# Cat_feeder.net
KiCad netlist of a schematic drawn in Altium Designer
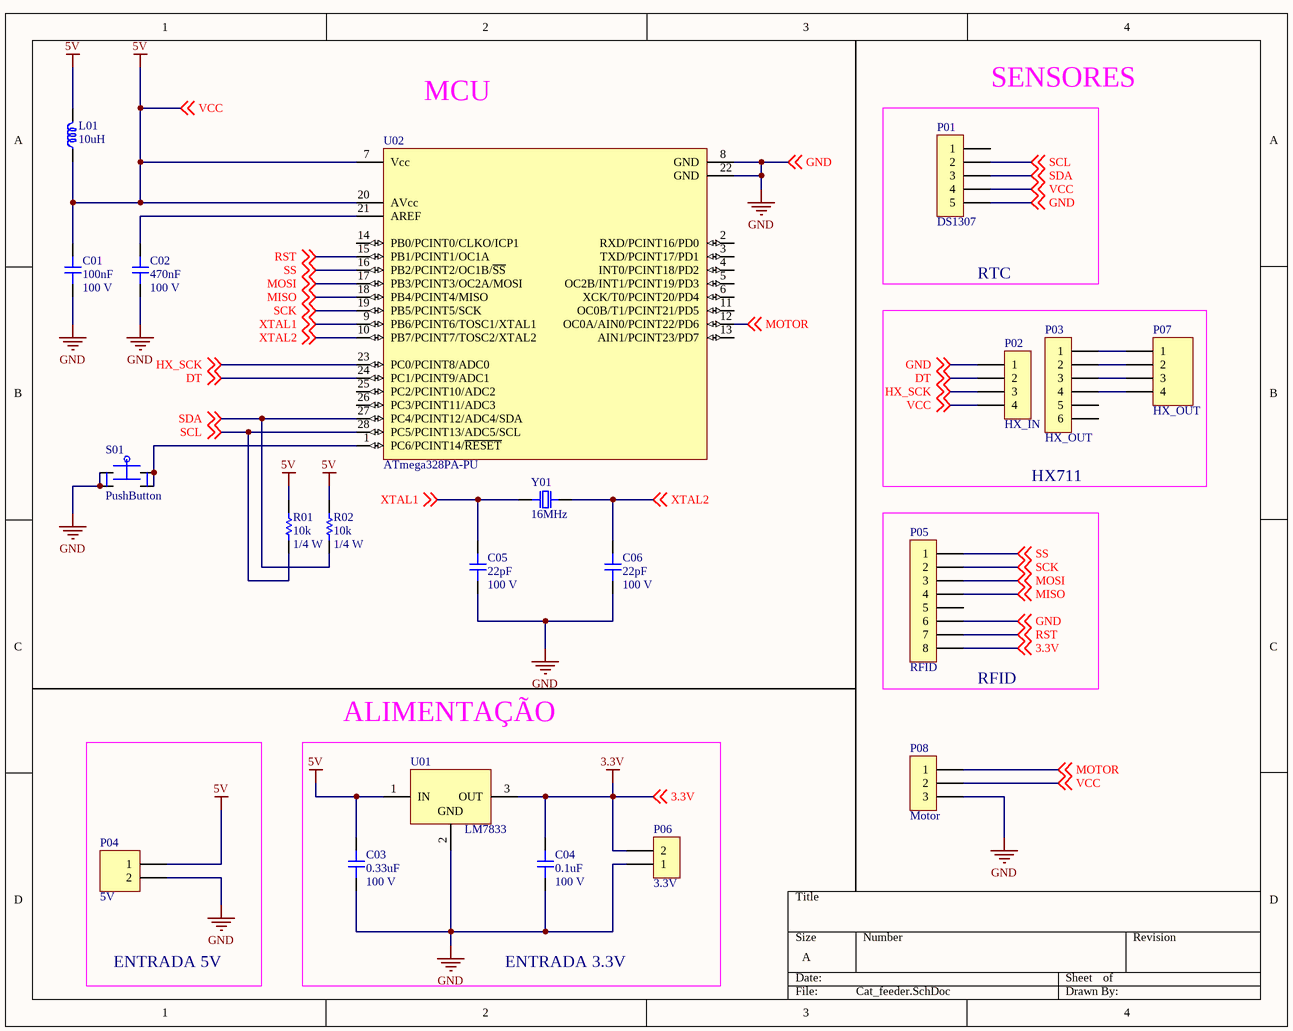
[diagram p0: Cat_feeder.SchDoc]

(export (version "E")
  (design (tool "Eeschema 10.0.6"))
  (components
    (comp (ref "C01")
      (value "100nF")
      (footprint "C100-200-100")
      (description "Capacitor")
      (fields (field (name "VOLTAGE") "100 V") (field (name "PUBLISHER") "Altium Limited"))
      (libsource (lib "GPDSE") (part "Capacitor"))
    )
    (comp (ref "C02")
      (value "470nF")
      (footprint "C100-200-100")
      (description "Capacitor")
      (fields (field (name "VOLTAGE") "100 V") (field (name "PUBLISHER") "Altium Limited"))
      (libsource (lib "GPDSE") (part "Capacitor"))
    )
    (comp (ref "C03")
      (value "0.33uF")
      (footprint "C200-350-150")
      (description "Capacitor")
      (fields (field (name "VOLTAGE") "100 V") (field (name "PUBLISHER") "Altium Limited"))
      (libsource (lib "GPDSE") (part "Capacitor"))
    )
    (comp (ref "C04")
      (value "0.1uF")
      (footprint "C200-350-150")
      (description "Capacitor")
      (fields (field (name "VOLTAGE") "100 V") (field (name "PUBLISHER") "Altium Limited"))
      (libsource (lib "GPDSE") (part "Capacitor"))
    )
    (comp (ref "C05")
      (value "22pF")
      (footprint "C100-200-100")
      (description "Capacitor")
      (fields (field (name "VOLTAGE") "100 V") (field (name "PUBLISHER") "Altium Limited"))
      (libsource (lib "GPDSE") (part "Capacitor"))
    )
    (comp (ref "C06")
      (value "22pF")
      (footprint "C100-200-100")
      (description "Capacitor")
      (fields (field (name "VOLTAGE") "100 V") (field (name "PUBLISHER") "Altium Limited"))
      (libsource (lib "GPDSE") (part "Capacitor"))
    )
    (comp (ref "L01")
      (value "10uH")
      (footprint "L400-2.0mm")
      (description "Inductor")
      (libsource (lib "GPDSE") (part "Inductor"))
    )
    (comp (ref "P01")
      (value "DS1307")
      (footprint "HDR-M-1x5-2.54mm-180-9.2mm")
      (description "Header, 1 Line, 5 Columns, 5 Pins")
      (fields (field (name "PUBLISHER") "Altium Limited"))
      (libsource (lib "GPDSE") (part "Header_1x5"))
    )
    (comp (ref "P02")
      (value "HX_IN")
      (footprint "HDR-M-1x4-2.54mm-180-21.1mm")
      (description "Header, 1 Line, 4 Columns, 4 Pins")
      (fields (field (name "PUBLISHER") "Altium Limited"))
      (libsource (lib "GPDSE") (part "Header_1x4"))
    )
    (comp (ref "P03")
      (value "HX_OUT")
      (footprint "HDR-M-1x6-2.54mm-180-9.2mm")
      (description "Header, 1 Line, 6 Columns, 6 Pins")
      (fields (field (name "PUBLISHER") "Altium Limited"))
      (libsource (lib "GPDSE") (part "Header_1x6"))
    )
    (comp (ref "P04")
      (value "5V")
      (footprint "KRE_2")
      (description "Terminal Block 1x2")
      (libsource (lib "GPDSE") (part "KRE_2"))
    )
    (comp (ref "P05")
      (value "RFID")
      (footprint "HDR-M-1x8-2.54mm-180-9.2mm")
      (description "Header, 1 Line, 8 Columns, 8 Pins")
      (fields (field (name "PUBLISHER") "Altium Limited"))
      (libsource (lib "GPDSE") (part "Header_1x8"))
    )
    (comp (ref "P06")
      (value "3.3V")
      (footprint "HDR-M-1x2-2.54mm-180-9.2mm")
      (description "Header, 1 Line, 2 Columns, 2 Pins")
      (fields (field (name "PUBLISHER") "Altium Limited"))
      (libsource (lib "GPDSE") (part "Header_1x2"))
    )
    (comp (ref "P07")
      (value "HX_OUT")
      (footprint "KRE_4")
      (description "Terminal Block 1x4")
      (libsource (lib "GPDSE") (part "KRE_4"))
    )
    (comp (ref "P08")
      (value "Motor")
      (footprint "HDR-M-1x3-2.54mm-180-9.2mm")
      (description "Header, 1 Line, 3 Columns, 3 Pins")
      (fields (field (name "PUBLISHER") "Altium Limited"))
      (libsource (lib "GPDSE") (part "Header_1x3"))
    )
    (comp (ref "R01")
      (value "10k")
      (footprint "R400-2.0mm")
      (description "Resistor")
      (fields
        (field (name "TOLERANCE") "5%")
        (field (name "POWER") "1/4 W")
        (field (name "PUBLISHER") "Altium Limited")
      )
      (libsource (lib "GPDSE") (part "Resistor"))
    )
    (comp (ref "R02")
      (value "10k")
      (footprint "R400-2.0mm")
      (description "Resistor")
      (fields
        (field (name "TOLERANCE") "5%")
        (field (name "POWER") "1/4 W")
        (field (name "PUBLISHER") "Altium Limited")
      )
      (libsource (lib "GPDSE") (part "Resistor"))
    )
    (comp (ref "S01")
      (value "PushButton")
      (footprint "DTS-6.0mm-6.0mm-THT")
      (description "Tactile Switch SPST 4 pins")
      (libsource (lib "GPDSE") (part "PushButton_4"))
    )
    (comp (ref "U01")
      (value "LM7833")
      (footprint "TO-220/123")
      (description "3-Terminal 1 A Positive 5 V Voltage Regulator")
      (libsource (lib "GPDSE") (part "LM7805CT"))
    )
    (comp (ref "U02")
      (value "ATmega328PA-PU")
      (footprint "DIP28-300(100)")
      (description "8-bit AVR Microcontroller with 32 KB In-System Programmable Flash")
      (libsource (lib "GPDSE") (part "ATmega328PA-PU"))
    )
    (comp (ref "Y01")
      (value "16MHz")
      (footprint "HC49-US-THT")
      (description "Crystal")
      (libsource (lib "GPDSE") (part "Crystal"))
    )
  )
  (nets
    (net (code "1") (name "3.3V") (class "Default")
      (node (ref "C04") (pin "2") (pinfunction "2_2") (pintype "passive"))
      (node (ref "P05") (pin "8") (pinfunction "8_8") (pintype "passive"))
      (node (ref "P06") (pin "2") (pinfunction "2_2") (pintype "passive"))
      (node (ref "U01") (pin "3") (pinfunction "OUT_3") (pintype "passive"))
    )
    (net (code "2") (name "5V") (class "Default")
      (node (ref "C01") (pin "2") (pinfunction "2_2") (pintype "passive"))
      (node (ref "C03") (pin "2") (pinfunction "2_2") (pintype "passive"))
      (node (ref "L01") (pin "1") (pinfunction "1_1") (pintype "passive"))
      (node (ref "L01") (pin "2") (pinfunction "2_2") (pintype "passive"))
      (node (ref "P01") (pin "4") (pinfunction "4_4") (pintype "passive"))
      (node (ref "P02") (pin "4") (pinfunction "4_4") (pintype "passive"))
      (node (ref "P04") (pin "1") (pinfunction "1_1") (pintype "passive"))
      (node (ref "P08") (pin "2") (pinfunction "2_2") (pintype "passive"))
      (node (ref "R01") (pin "2") (pinfunction "2_2") (pintype "passive"))
      (node (ref "R02") (pin "2") (pinfunction "2_2") (pintype "passive"))
      (node (ref "U01") (pin "1") (pinfunction "IN_1") (pintype "passive"))
      (node (ref "U02") (pin "20") (pinfunction "AVcc_20") (pintype "passive"))
      (node (ref "U02") (pin "7") (pinfunction "Vcc_7") (pintype "passive"))
    )
    (net (code "3") (name "DT") (class "Default")
      (node (ref "P02") (pin "2") (pinfunction "2_2") (pintype "passive"))
      (node (ref "U02") (pin "24") (pinfunction "PC1/PCINT9/ADC1_24") (pintype "bidirectional"))
    )
    (net (code "4") (name "GND") (class "Default")
      (node (ref "C01") (pin "1") (pinfunction "1_1") (pintype "passive"))
      (node (ref "C02") (pin "1") (pinfunction "1_1") (pintype "passive"))
      (node (ref "C03") (pin "1") (pinfunction "1_1") (pintype "passive"))
      (node (ref "C04") (pin "1") (pinfunction "1_1") (pintype "passive"))
      (node (ref "C05") (pin "1") (pinfunction "1_1") (pintype "passive"))
      (node (ref "C06") (pin "1") (pinfunction "1_1") (pintype "passive"))
      (node (ref "P01") (pin "5") (pinfunction "5_5") (pintype "passive"))
      (node (ref "P02") (pin "1") (pinfunction "1_1") (pintype "passive"))
      (node (ref "P04") (pin "2") (pinfunction "2_2") (pintype "passive"))
      (node (ref "P05") (pin "6") (pinfunction "6_6") (pintype "passive"))
      (node (ref "P06") (pin "1") (pinfunction "1_1") (pintype "passive"))
      (node (ref "P08") (pin "3") (pinfunction "3_3") (pintype "passive"))
      (node (ref "S01") (pin "1") (pinfunction "1_1") (pintype "passive"))
      (node (ref "S01") (pin "2") (pinfunction "2_2") (pintype "passive"))
      (node (ref "U01") (pin "2") (pinfunction "GND_2") (pintype "passive"))
      (node (ref "U02") (pin "22") (pinfunction "GND_22") (pintype "passive"))
      (node (ref "U02") (pin "8") (pinfunction "GND_8") (pintype "passive"))
    )
    (net (code "5") (name "HX_SCK") (class "Default")
      (node (ref "P02") (pin "3") (pinfunction "3_3") (pintype "passive"))
      (node (ref "U02") (pin "23") (pinfunction "PC0/PCINT8/ADC0_23") (pintype "bidirectional"))
    )
    (net (code "6") (name "MISO") (class "Default")
      (node (ref "P05") (pin "4") (pinfunction "4_4") (pintype "passive"))
      (node (ref "U02") (pin "18") (pinfunction "PB4/PCINT4/MISO_18") (pintype "bidirectional"))
    )
    (net (code "7") (name "MOSI") (class "Default")
      (node (ref "P05") (pin "3") (pinfunction "3_3") (pintype "passive"))
      (node (ref "U02") (pin "17") (pinfunction "PB3/PCINT3/OC2A/MOSI_17") (pintype "bidirectional"))
    )
    (net (code "8") (name "MOTOR") (class "Default")
      (node (ref "P08") (pin "1") (pinfunction "1_1") (pintype "passive"))
      (node (ref "U02") (pin "12") (pinfunction "OC0A/AIN0/PCINT22/PD6_12") (pintype "bidirectional"))
    )
    (net (code "9") (name "Net-(P03-Pad1)") (class "Default")
      (node (ref "P03") (pin "1") (pinfunction "1_1") (pintype "passive"))
      (node (ref "P07") (pin "1") (pinfunction "1_1") (pintype "passive"))
    )
    (net (code "10") (name "Net-(P03-Pad2)") (class "Default")
      (node (ref "P03") (pin "2") (pinfunction "2_2") (pintype "passive"))
      (node (ref "P07") (pin "2") (pinfunction "2_2") (pintype "passive"))
    )
    (net (code "11") (name "Net-(P03-Pad3)") (class "Default")
      (node (ref "P03") (pin "3") (pinfunction "3_3") (pintype "passive"))
      (node (ref "P07") (pin "3") (pinfunction "3_3") (pintype "passive"))
    )
    (net (code "12") (name "Net-(P03-Pad4)") (class "Default")
      (node (ref "P03") (pin "4") (pinfunction "4_4") (pintype "passive"))
      (node (ref "P07") (pin "4") (pinfunction "4_4") (pintype "passive"))
    )
    (net (code "13") (name "Net-(U02-AREF)") (class "Default")
      (node (ref "C02") (pin "2") (pinfunction "2_2") (pintype "passive"))
      (node (ref "U02") (pin "21") (pinfunction "AREF_21") (pintype "passive"))
    )
    (net (code "14") (name "Net-(U02-PC6{slash}PCINT14{slash}~{RESET})") (class "Default")
      (node (ref "S01") (pin "3") (pinfunction "3_3") (pintype "passive"))
      (node (ref "S01") (pin "4") (pinfunction "4_4") (pintype "passive"))
      (node (ref "U02") (pin "1") (pinfunction "PC6/PCINT14/~{RESET}_1") (pintype "bidirectional"))
    )
    (net (code "15") (name "RST") (class "Default")
      (node (ref "P05") (pin "7") (pinfunction "7_7") (pintype "passive"))
      (node (ref "U02") (pin "15") (pinfunction "PB1/PCINT1/OC1A_15") (pintype "bidirectional"))
    )
    (net (code "16") (name "SCK") (class "Default")
      (node (ref "P05") (pin "2") (pinfunction "2_2") (pintype "passive"))
      (node (ref "U02") (pin "19") (pinfunction "PB5/PCINT5/SCK_19") (pintype "bidirectional"))
    )
    (net (code "17") (name "SCL") (class "Default")
      (node (ref "P01") (pin "2") (pinfunction "2_2") (pintype "passive"))
      (node (ref "R01") (pin "1") (pinfunction "1_1") (pintype "passive"))
      (node (ref "U02") (pin "28") (pinfunction "PC5/PCINT13/ADC5/SCL_28") (pintype "bidirectional"))
    )
    (net (code "18") (name "SDA") (class "Default")
      (node (ref "P01") (pin "3") (pinfunction "3_3") (pintype "passive"))
      (node (ref "R02") (pin "1") (pinfunction "1_1") (pintype "passive"))
      (node (ref "U02") (pin "27") (pinfunction "PC4/PCINT12/ADC4/SDA_27") (pintype "bidirectional"))
    )
    (net (code "19") (name "SS") (class "Default")
      (node (ref "P05") (pin "1") (pinfunction "1_1") (pintype "passive"))
      (node (ref "U02") (pin "16") (pinfunction "PB2/PCINT2/OC1B/~{SS}_16") (pintype "bidirectional"))
    )
    (net (code "20") (name "XTAL1") (class "Default")
      (node (ref "C05") (pin "2") (pinfunction "2_2") (pintype "passive"))
      (node (ref "U02") (pin "9") (pinfunction "PB6/PCINT6/TOSC1/XTAL1_9") (pintype "bidirectional"))
      (node (ref "Y01") (pin "1") (pinfunction "1_1") (pintype "passive"))
    )
    (net (code "21") (name "XTAL2") (class "Default")
      (node (ref "C06") (pin "2") (pinfunction "2_2") (pintype "passive"))
      (node (ref "U02") (pin "10") (pinfunction "PB7/PCINT7/TOSC2/XTAL2_10") (pintype "bidirectional"))
      (node (ref "Y01") (pin "2") (pinfunction "2_2") (pintype "passive"))
    )
    (net (code "22") (name "unconnected-(P01-Pad1)") (class "Default")
      (node (ref "P01") (pin "1") (pinfunction "1_1") (pintype "passive"))
    )
    (net (code "23") (name "unconnected-(P03-Pad5)") (class "Default")
      (node (ref "P03") (pin "5") (pinfunction "5_5") (pintype "passive"))
    )
    (net (code "24") (name "unconnected-(P03-Pad6)") (class "Default")
      (node (ref "P03") (pin "6") (pinfunction "6_6") (pintype "passive"))
    )
    (net (code "25") (name "unconnected-(P05-Pad5)") (class "Default")
      (node (ref "P05") (pin "5") (pinfunction "5_5") (pintype "passive"))
    )
    (net (code "26") (name "unconnected-(U02-AIN1{slash}PCINT23{slash}PD7-Pad13)") (class "Default")
      (node (ref "U02") (pin "13") (pinfunction "AIN1/PCINT23/PD7_13") (pintype "bidirectional"))
    )
    (net (code "27") (name "unconnected-(U02-INT0{slash}PCINT18{slash}PD2-Pad4)") (class "Default")
      (node (ref "U02") (pin "4") (pinfunction "INT0/PCINT18/PD2_4") (pintype "bidirectional"))
    )
    (net (code "28") (name "unconnected-(U02-OC0B{slash}T1{slash}PCINT21{slash}PD5-Pad11)") (class "Default")
      (node (ref "U02") (pin "11") (pinfunction "OC0B/T1/PCINT21/PD5_11") (pintype "bidirectional"))
    )
    (net (code "29") (name "unconnected-(U02-OC2B{slash}INT1{slash}PCINT19{slash}PD3-Pad5)") (class "Default")
      (node (ref "U02") (pin "5") (pinfunction "OC2B/INT1/PCINT19/PD3_5") (pintype "bidirectional"))
    )
    (net (code "30") (name "unconnected-(U02-PB0{slash}PCINT0{slash}CLKO{slash}ICP1-Pad14)") (class "Default")
      (node (ref "U02") (pin "14") (pinfunction "PB0/PCINT0/CLKO/ICP1_14") (pintype "bidirectional"))
    )
    (net (code "31") (name "unconnected-(U02-PC2{slash}PCINT10{slash}ADC2-Pad25)") (class "Default")
      (node (ref "U02") (pin "25") (pinfunction "PC2/PCINT10/ADC2_25") (pintype "bidirectional"))
    )
    (net (code "32") (name "unconnected-(U02-PC3{slash}PCINT11{slash}ADC3-Pad26)") (class "Default")
      (node (ref "U02") (pin "26") (pinfunction "PC3/PCINT11/ADC3_26") (pintype "bidirectional"))
    )
    (net (code "33") (name "unconnected-(U02-RXD{slash}PCINT16{slash}PD0-Pad2)") (class "Default")
      (node (ref "U02") (pin "2") (pinfunction "RXD/PCINT16/PD0_2") (pintype "bidirectional"))
    )
    (net (code "34") (name "unconnected-(U02-TXD{slash}PCINT17{slash}PD1-Pad3)") (class "Default")
      (node (ref "U02") (pin "3") (pinfunction "TXD/PCINT17/PD1_3") (pintype "bidirectional"))
    )
    (net (code "35") (name "unconnected-(U02-XCK{slash}T0{slash}PCINT20{slash}PD4-Pad6)") (class "Default")
      (node (ref "U02") (pin "6") (pinfunction "XCK/T0/PCINT20/PD4_6") (pintype "bidirectional"))
    )
  )
)
